# led.net
KiCad netlist of a schematic drawn in Altium Designer
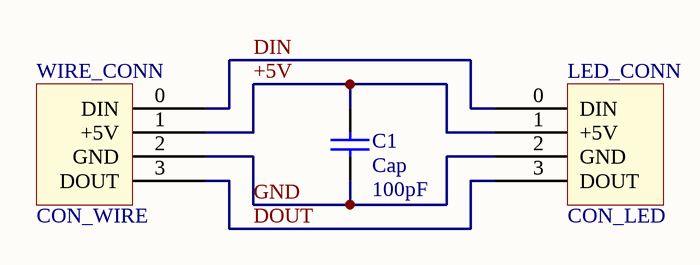
[diagram p0: led.SchDoc]

(export (version "E")
  (design (tool "Eeschema 10.0.6"))
  (components
    (comp (ref "C1")
      (value "Cap")
      (footprint "RAD-0.3")
      (description "Capacitor")
      (fields (field (name "ALTIUM_VALUE") "100pF") (field (name "PUBLISHER") "Altium Limited"))
      (libsource (lib "Miscellaneous Devices") (part "Cap"))
    )
    (comp (ref "LED_CONN") (value "CON_LED") (libsource (lib "led_Schlib") (part "CON_LED")))
    (comp (ref "WIRE_CONN") (value "CON_WIRE") (libsource (lib "led_Schlib") (part "CON_WIRE")))
  )
  (nets
    (net (code "1") (name "/+5V") (class "Default")
      (node (ref "C1") (pin "2") (pinfunction "2_2") (pintype "passive"))
      (node (ref "LED_CONN") (pin "1") (pinfunction "+5V_1") (pintype "passive"))
      (node (ref "WIRE_CONN") (pin "1") (pinfunction "+5V_1") (pintype "passive"))
    )
    (net (code "2") (name "/DIN") (class "Default")
      (node (ref "LED_CONN") (pin "0") (pinfunction "DIN_0") (pintype "passive"))
      (node (ref "WIRE_CONN") (pin "0") (pinfunction "DIN_0") (pintype "passive"))
    )
    (net (code "3") (name "/DOUT") (class "Default")
      (node (ref "LED_CONN") (pin "3") (pinfunction "DOUT_3") (pintype "passive"))
      (node (ref "WIRE_CONN") (pin "3") (pinfunction "DOUT_3") (pintype "passive"))
    )
    (net (code "4") (name "/GND") (class "Default")
      (node (ref "C1") (pin "1") (pinfunction "1_1") (pintype "passive"))
      (node (ref "LED_CONN") (pin "2") (pinfunction "GND_2") (pintype "passive"))
      (node (ref "WIRE_CONN") (pin "2") (pinfunction "GND_2") (pintype "passive"))
    )
  )
)
